# Relay.net
KiCad netlist of a schematic drawn in Altium Designer
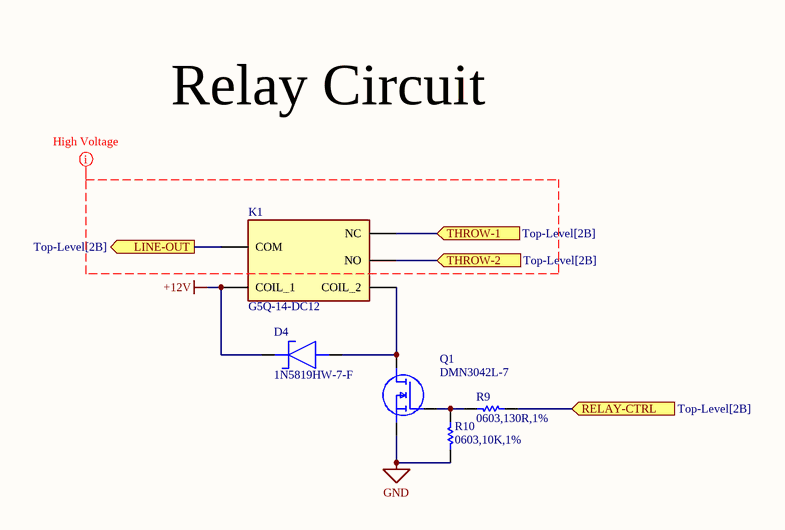
[diagram p0: Relay.SchDoc]

(export (version "E")
  (design (tool "Eeschema 10.0.6"))
  (components
    (comp (ref "D4")
      (value "1N5819HW-7-F")
      (footprint "SOD3716X145N")
      (description "40V 450mV@1A 1A SOD-123 Schottky Diodes ROHS")
      (fields (field (name "MOUSER PART NUMBER") "621-1N5819HW-F") (field (name "LCSC PART NUMBER") "C82544"))
      (libsource (lib "LC-SchLib") (part "1N5819HW-7-F"))
    )
    (comp (ref "K1")
      (value "G5Q-14-DC12")
      (footprint "G5Q14DC12")
      (description "12V 10A 1 Form C: 1C (SPDT-CO) Through Hole,10x20mm Power Relays ROHS")
      (fields
        (field (name "MOUSER PART NUMBER") "653-G5Q-14-DC12")
        (field (name "LCSC PART NUMBER") "C225715")
      )
      (libsource (lib "LC-SchLib") (part "G5Q-14-DC12"))
    )
    (comp (ref "Q1")
      (value "DMN3042L-7")
      (footprint "SOT96P240X115-3N")
      (description "N-Channel 30 V 5.8A (Ta) 720mW (Ta) Surface Mount SOT-23-3")
      (fields
        (field (name "MOUSER PART NUMBER") "621-DMN3042L-7")
        (field (name "LCSC PART NUMBER") "C2838502")
      )
      (libsource (lib "LC-SchLib") (part "DMN3042L-7"))
    )
    (comp (ref "R9")
      (value "0603,130R,1%")
      (footprint "RESC1608X55N")
      (description "130 Ohms ±1% 0.1W, 1/10W Chip Resistor 0603 (1608 Metric) Moisture Resistant Thick Film")
      (fields
        (field (name "MANUFACTURER_PART_NUMBER") "RC0603FR-07130RL")
        (field (name "LCSC PART NUMBER") "C141677")
      )
      (libsource (lib "LC-SchLib") (part "RC0603FR-07130RL"))
    )
    (comp (ref "R10")
      (value "0603,10K,1%")
      (footprint "RESC1608X55N")
      (description "100mW Thick Film Resistor 75V ±100ppm/℃ ±1% 10kΩ 0603 Chip Resistor - Surface Mount ROHS")
      (fields
        (field (name "MANUFACTURER_PART_NUMBER") "RC0603FR-0710KL")
        (field (name "MOUSER PART NUMBER") "603-RC0603FR-0710KL")
      )
      (libsource (lib "LC-SchLib") (part "RC0603FR-0710KL"))
    )
  )
  (nets
    (net (code "1") (name "+12V") (class "Default")
      (node (ref "D4") (pin "1") (pinfunction "K_1") (pintype "passive"))
      (node (ref "K1") (pin "1") (pinfunction "COIL_1_1") (pintype "passive"))
    )
    (net (code "2") (name "/LINE-OUT") (class "Default")
      (node (ref "K1") (pin "2") (pinfunction "COM_2") (pintype "passive"))
    )
    (net (code "3") (name "/RELAY-CTRL") (class "Default")
      (node (ref "R9") (pin "1") (pinfunction "1_1") (pintype "passive"))
    )
    (net (code "4") (name "/THROW-1") (class "Default")
      (node (ref "K1") (pin "4") (pinfunction "NC_4") (pintype "passive"))
    )
    (net (code "5") (name "/THROW-2") (class "Default")
      (node (ref "K1") (pin "3") (pinfunction "NO_3") (pintype "passive"))
    )
    (net (code "6") (name "GND") (class "Default")
      (node (ref "Q1") (pin "2") (pinfunction "S_2") (pintype "passive"))
      (node (ref "R10") (pin "1") (pinfunction "1_1") (pintype "passive"))
    )
    (net (code "7") (name "Net-(D4-A)") (class "Default")
      (node (ref "D4") (pin "2") (pinfunction "A_2") (pintype "passive"))
      (node (ref "K1") (pin "5") (pinfunction "COIL_2_5") (pintype "passive"))
      (node (ref "Q1") (pin "3") (pinfunction "D_3") (pintype "passive"))
    )
    (net (code "8") (name "Net-(Q1-G)") (class "Default")
      (node (ref "Q1") (pin "1") (pinfunction "G_1") (pintype "passive"))
      (node (ref "R10") (pin "2") (pinfunction "2_2") (pintype "passive"))
      (node (ref "R9") (pin "2") (pinfunction "2_2") (pintype "passive"))
    )
  )
)
